# working.net
KiCad netlist of a schematic drawn in EAGLE
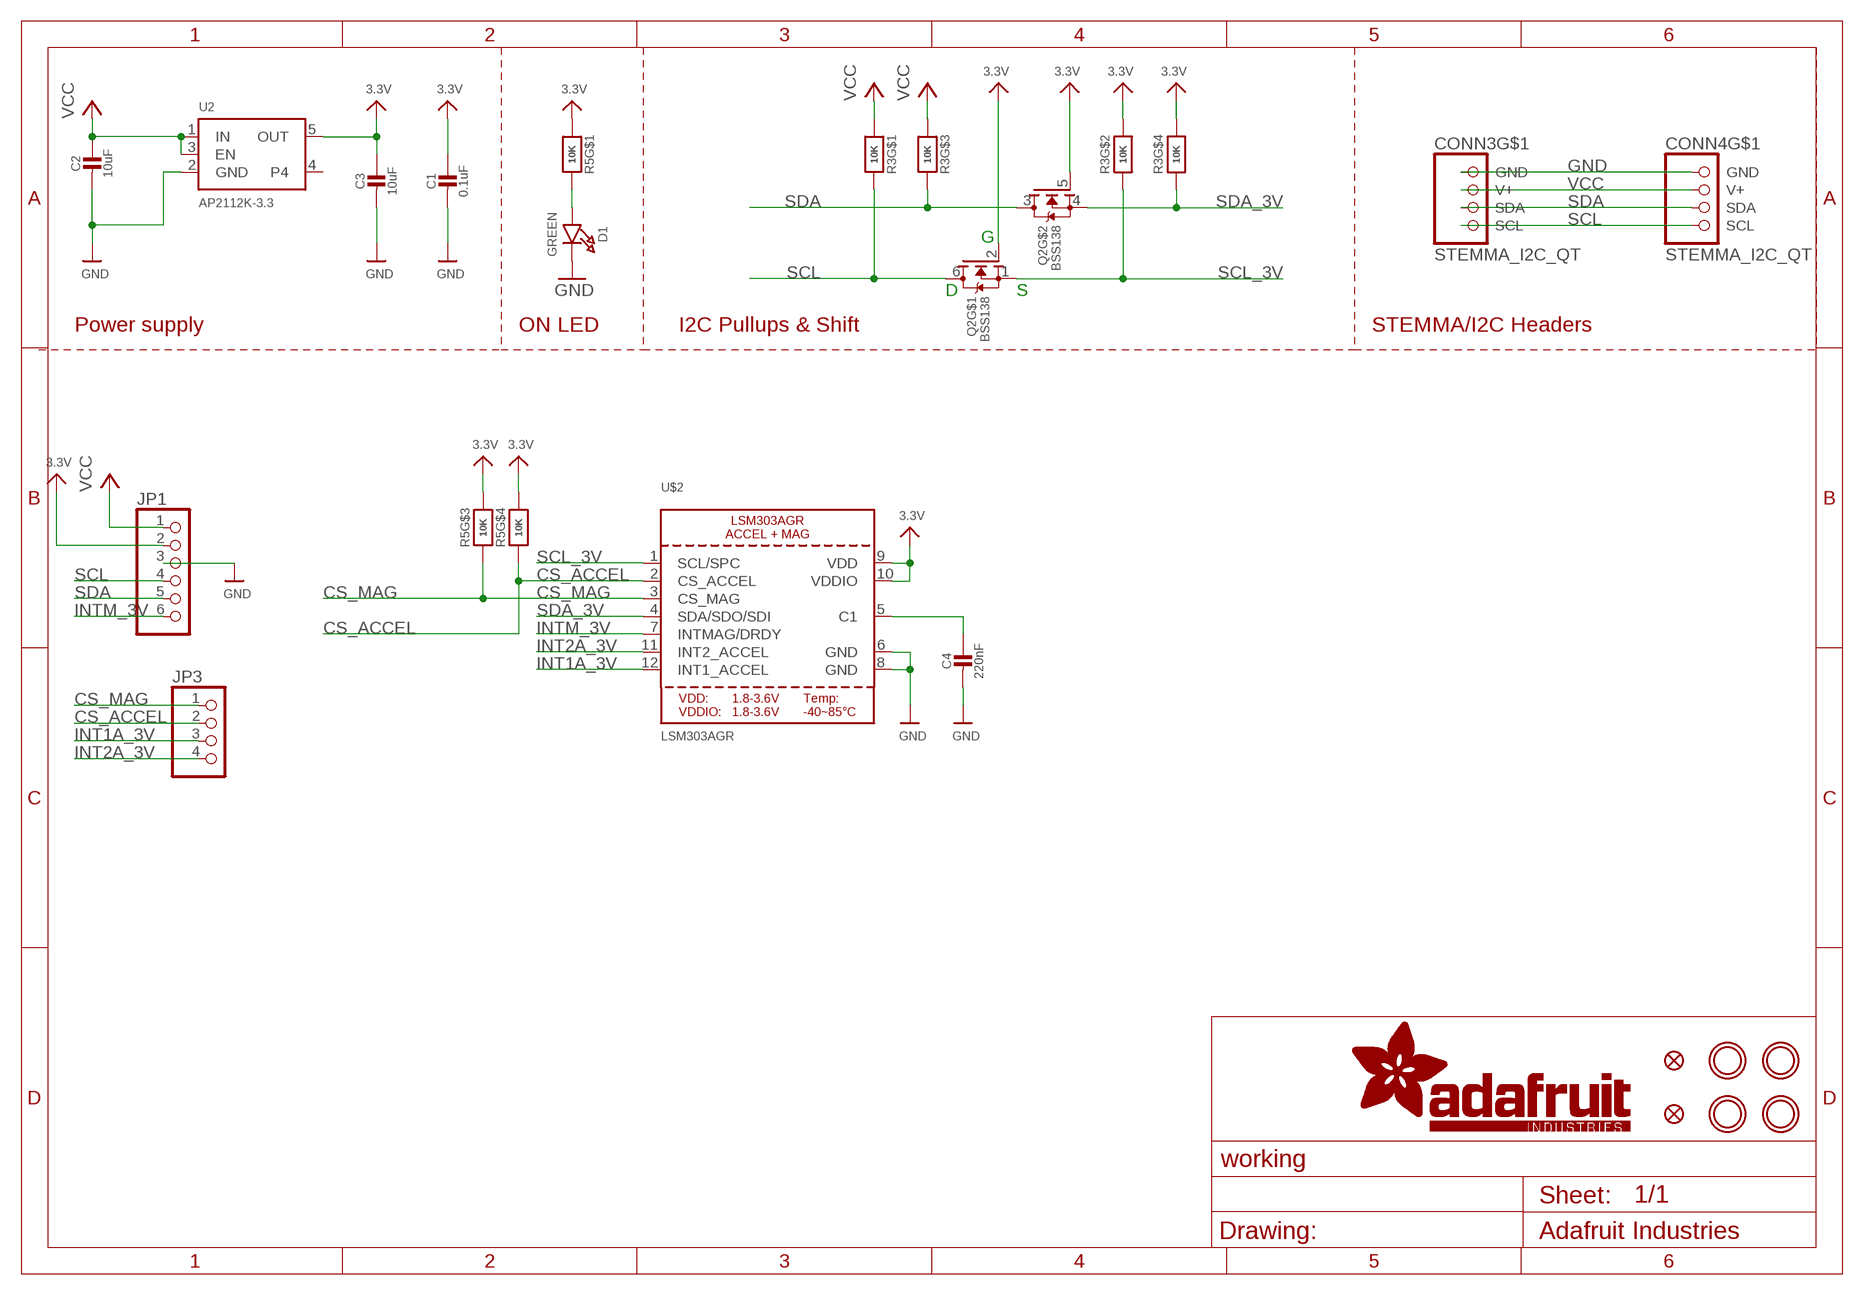
[diagram p0: schematic, sheet 1]

(export (version "E")
  (design (tool "Eeschema 10.0.6"))
  (components
    (comp (ref "C1")
      (value "0.1uF")
      (footprint "eagle-import:0603-NO@1")
      (libsource (lib "eagle-import") (part "CAP_CERAMIC0603_NO"))
    )
    (comp (ref "C2")
      (value "10uF")
      (footprint "eagle-import:0805-NO")
      (libsource (lib "eagle-import") (part "CAP_CERAMIC0805-NOOUTLINE"))
    )
    (comp (ref "C3")
      (value "10uF")
      (footprint "eagle-import:0805_10MGAP")
      (libsource (lib "eagle-import") (part "CAP_CERAMIC0805_10MGAP"))
    )
    (comp (ref "C4")
      (value "220nF")
      (footprint "eagle-import:0603-NO@1")
      (libsource (lib "eagle-import") (part "CAP_CERAMIC0603_NO"))
    )
    (comp (ref "CONN3")
      (value "STEMMA_I2C_QT")
      (footprint "eagle-import:JST_SH4")
      (libsource (lib "eagle-import") (part "STEMMA_I2C_QT"))
    )
    (comp (ref "CONN4")
      (value "STEMMA_I2C_QT")
      (footprint "eagle-import:JST_SH4")
      (libsource (lib "eagle-import") (part "STEMMA_I2C_QT"))
    )
    (comp (ref "D1")
      (value "GREEN")
      (footprint "eagle-import:CHIPLED_0603_NOOUTLINE")
      (libsource (lib "eagle-import") (part "LED0603_NOOUTLINE"))
    )
    (comp (ref "FID3")
      (value "FIDUCIAL_1MM")
      (footprint "eagle-import:FIDUCIAL_1MM")
      (libsource (lib "eagle-import") (part "FIDUCIAL_1MM"))
    )
    (comp (ref "FID4")
      (value "FIDUCIAL_1MM")
      (footprint "eagle-import:FIDUCIAL_1MM")
      (libsource (lib "eagle-import") (part "FIDUCIAL_1MM"))
    )
    (comp (ref "JP1")
      (value "HEADER-1X670MIL")
      (footprint "eagle-import:1X06_ROUND_70")
      (libsource (lib "eagle-import") (part "HEADER-1X670MIL"))
    )
    (comp (ref "JP3")
      (value "HEADER-1X4ROUND")
      (footprint "eagle-import:1X04_ROUND")
      (libsource (lib "eagle-import") (part "HEADER-1X4ROUND"))
    )
    (comp (ref "Q2")
      (value "BSS138")
      (footprint "eagle-import:SOT363")
      (libsource (lib "eagle-import") (part "MOSFET-N_DUAL"))
    )
    (comp (ref "R3")
      (value "10K")
      (footprint "eagle-import:RESPACK_4X0603")
      (libsource (lib "eagle-import") (part "RESISTOR_4PACK"))
    )
    (comp (ref "R5")
      (value "10K")
      (footprint "eagle-import:RESPACK_4X0603")
      (libsource (lib "eagle-import") (part "RESISTOR_4PACK"))
    )
    (comp (ref "U$1")
      (value "MOUNTINGHOLE2.5")
      (footprint "eagle-import:MOUNTINGHOLE_2.5_PLATED")
      (libsource (lib "eagle-import") (part "MOUNTINGHOLE2.5"))
    )
    (comp (ref "U$2")
      (value "LSM303AGR")
      (footprint "eagle-import:LGA12_2X2MM")
      (libsource (lib "eagle-import") (part "LSM303AGR"))
    )
    (comp (ref "U$17")
      (value "MOUNTINGHOLE2.5")
      (footprint "eagle-import:MOUNTINGHOLE_2.5_PLATED")
      (libsource (lib "eagle-import") (part "MOUNTINGHOLE2.5"))
    )
    (comp (ref "U$19")
      (value "MOUNTINGHOLE2.5")
      (footprint "eagle-import:MOUNTINGHOLE_2.5_PLATED")
      (libsource (lib "eagle-import") (part "MOUNTINGHOLE2.5"))
    )
    (comp (ref "U$21")
      (value "MOUNTINGHOLE2.5")
      (footprint "eagle-import:MOUNTINGHOLE_2.5_PLATED")
      (libsource (lib "eagle-import") (part "MOUNTINGHOLE2.5"))
    )
    (comp (ref "U2")
      (value "AP2112K-3.3")
      (footprint "eagle-import:SOT23-5")
      (libsource (lib "eagle-import") (part "VREG_SOT23-5"))
    )
  )
  (nets
    (net (code "1") (name "/CS_ACCEL") (class "Default")
      (node (ref "JP3") (pin "2") (pinfunction "2_2") (pintype "passive"))
      (node (ref "R5") (pin "4") (pinfunction "1_4") (pintype "passive"))
      (node (ref "U$2") (pin "2") (pinfunction "CS_ACCEL_2") (pintype "input"))
    )
    (net (code "2") (name "/CS_MAG") (class "Default")
      (node (ref "JP3") (pin "1") (pinfunction "1_1") (pintype "passive"))
      (node (ref "R5") (pin "3") (pinfunction "1_3") (pintype "passive"))
      (node (ref "U$2") (pin "3") (pinfunction "CS_MAG_3") (pintype "input"))
    )
    (net (code "3") (name "/INT1A_3V") (class "Default")
      (node (ref "JP3") (pin "3") (pinfunction "3_3") (pintype "passive"))
      (node (ref "U$2") (pin "12") (pinfunction "INT1_ACCEL_12") (pintype "output"))
    )
    (net (code "4") (name "/INT2A_3V") (class "Default")
      (node (ref "JP3") (pin "4") (pinfunction "4_4") (pintype "passive"))
      (node (ref "U$2") (pin "11") (pinfunction "INT2_ACCEL_11") (pintype "output"))
    )
    (net (code "5") (name "/INTM_3V") (class "Default")
      (node (ref "JP1") (pin "6") (pinfunction "6_6") (pintype "passive"))
      (node (ref "U$2") (pin "7") (pinfunction "INTMAG/DRDY_7") (pintype "output"))
    )
    (net (code "6") (name "/SCL") (class "Default")
      (node (ref "CONN3") (pin "4") (pinfunction "SCL_4") (pintype "passive"))
      (node (ref "CONN4") (pin "4") (pinfunction "SCL_4") (pintype "passive"))
      (node (ref "JP1") (pin "4") (pinfunction "4_4") (pintype "passive"))
      (node (ref "Q2") (pin "6") (pinfunction "D_6") (pintype "bidirectional"))
      (node (ref "R3") (pin "8") (pinfunction "2_8") (pintype "passive"))
    )
    (net (code "7") (name "/SCL_3V") (class "Default")
      (node (ref "Q2") (pin "1") (pinfunction "S_1") (pintype "bidirectional"))
      (node (ref "R3") (pin "7") (pinfunction "2_7") (pintype "passive"))
      (node (ref "U$2") (pin "1") (pinfunction "SCL/SPC_1") (pintype "input"))
    )
    (net (code "8") (name "/SDA") (class "Default")
      (node (ref "CONN3") (pin "3") (pinfunction "SDA_3") (pintype "passive"))
      (node (ref "CONN4") (pin "3") (pinfunction "SDA_3") (pintype "passive"))
      (node (ref "JP1") (pin "5") (pinfunction "5_5") (pintype "passive"))
      (node (ref "Q2") (pin "3") (pinfunction "D_3") (pintype "bidirectional"))
      (node (ref "R3") (pin "6") (pinfunction "2_6") (pintype "passive"))
    )
    (net (code "9") (name "/SDA_3V") (class "Default")
      (node (ref "Q2") (pin "4") (pinfunction "S_4") (pintype "bidirectional"))
      (node (ref "R3") (pin "5") (pinfunction "2_5") (pintype "passive"))
      (node (ref "U$2") (pin "4") (pinfunction "SDA/SDO/SDI_4") (pintype "bidirectional"))
    )
    (net (code "10") (name "3.3V") (class "Default")
      (node (ref "C1") (pin "1") (pinfunction "1_1") (pintype "passive"))
      (node (ref "C3") (pin "1") (pinfunction "1_1") (pintype "passive"))
      (node (ref "JP1") (pin "2") (pinfunction "2_2") (pintype "passive"))
      (node (ref "Q2") (pin "2") (pinfunction "G_2") (pintype "bidirectional"))
      (node (ref "Q2") (pin "5") (pinfunction "G_5") (pintype "bidirectional"))
      (node (ref "R3") (pin "2") (pinfunction "1_2") (pintype "passive"))
      (node (ref "R3") (pin "4") (pinfunction "1_4") (pintype "passive"))
      (node (ref "R5") (pin "1") (pinfunction "1_1") (pintype "passive"))
      (node (ref "R5") (pin "5") (pinfunction "2_5") (pintype "passive"))
      (node (ref "R5") (pin "6") (pinfunction "2_6") (pintype "passive"))
      (node (ref "U$2") (pin "10") (pinfunction "VDDIO_10") (pintype "power_in"))
      (node (ref "U$2") (pin "9") (pinfunction "VDD_9") (pintype "power_in"))
      (node (ref "U2") (pin "5") (pinfunction "OUT_5") (pintype "power_in"))
    )
    (net (code "11") (name "GND") (class "Default")
      (node (ref "C1") (pin "2") (pinfunction "2_2") (pintype "passive"))
      (node (ref "C2") (pin "2") (pinfunction "2_2") (pintype "passive"))
      (node (ref "C3") (pin "2") (pinfunction "2_2") (pintype "passive"))
      (node (ref "C4") (pin "2") (pinfunction "2_2") (pintype "passive"))
      (node (ref "CONN3") (pin "1") (pinfunction "GND_1") (pintype "passive"))
      (node (ref "CONN4") (pin "1") (pinfunction "GND_1") (pintype "passive"))
      (node (ref "D1") (pin "C") (pinfunction "C_C") (pintype "passive"))
      (node (ref "JP1") (pin "3") (pinfunction "3_3") (pintype "passive"))
      (node (ref "U$2") (pin "6") (pinfunction "GND_6") (pintype "power_in"))
      (node (ref "U$2") (pin "8") (pinfunction "GND_8") (pintype "power_in"))
      (node (ref "U2") (pin "2") (pinfunction "GND_2") (pintype "power_in"))
    )
    (net (code "12") (name "Net-(R5A-2)") (class "Default")
      (node (ref "D1") (pin "A") (pinfunction "A_A") (pintype "passive"))
      (node (ref "R5") (pin "8") (pinfunction "2_8") (pintype "passive"))
    )
    (net (code "13") (name "Net-(U$2-C1)") (class "Default")
      (node (ref "C4") (pin "1") (pinfunction "1_1") (pintype "passive"))
      (node (ref "U$2") (pin "5") (pinfunction "C1_5") (pintype "passive"))
    )
    (net (code "14") (name "VCC") (class "Default")
      (node (ref "C2") (pin "1") (pinfunction "1_1") (pintype "passive"))
      (node (ref "CONN3") (pin "2") (pinfunction "V+_2") (pintype "passive"))
      (node (ref "CONN4") (pin "2") (pinfunction "V+_2") (pintype "passive"))
      (node (ref "JP1") (pin "1") (pinfunction "1_1") (pintype "passive"))
      (node (ref "R3") (pin "1") (pinfunction "1_1") (pintype "passive"))
      (node (ref "R3") (pin "3") (pinfunction "1_3") (pintype "passive"))
      (node (ref "U2") (pin "1") (pinfunction "IN_1") (pintype "power_in"))
      (node (ref "U2") (pin "3") (pinfunction "EN_3") (pintype "input"))
    )
    (net (code "15") (name "unconnected-(U2-P4-Pad4)") (class "Default")
      (node (ref "U2") (pin "4") (pinfunction "P4_4") (pintype "bidirectional"))
    )
  )
)
